# OSSIICB.net
KiCad netlist of a schematic drawn in EAGLE
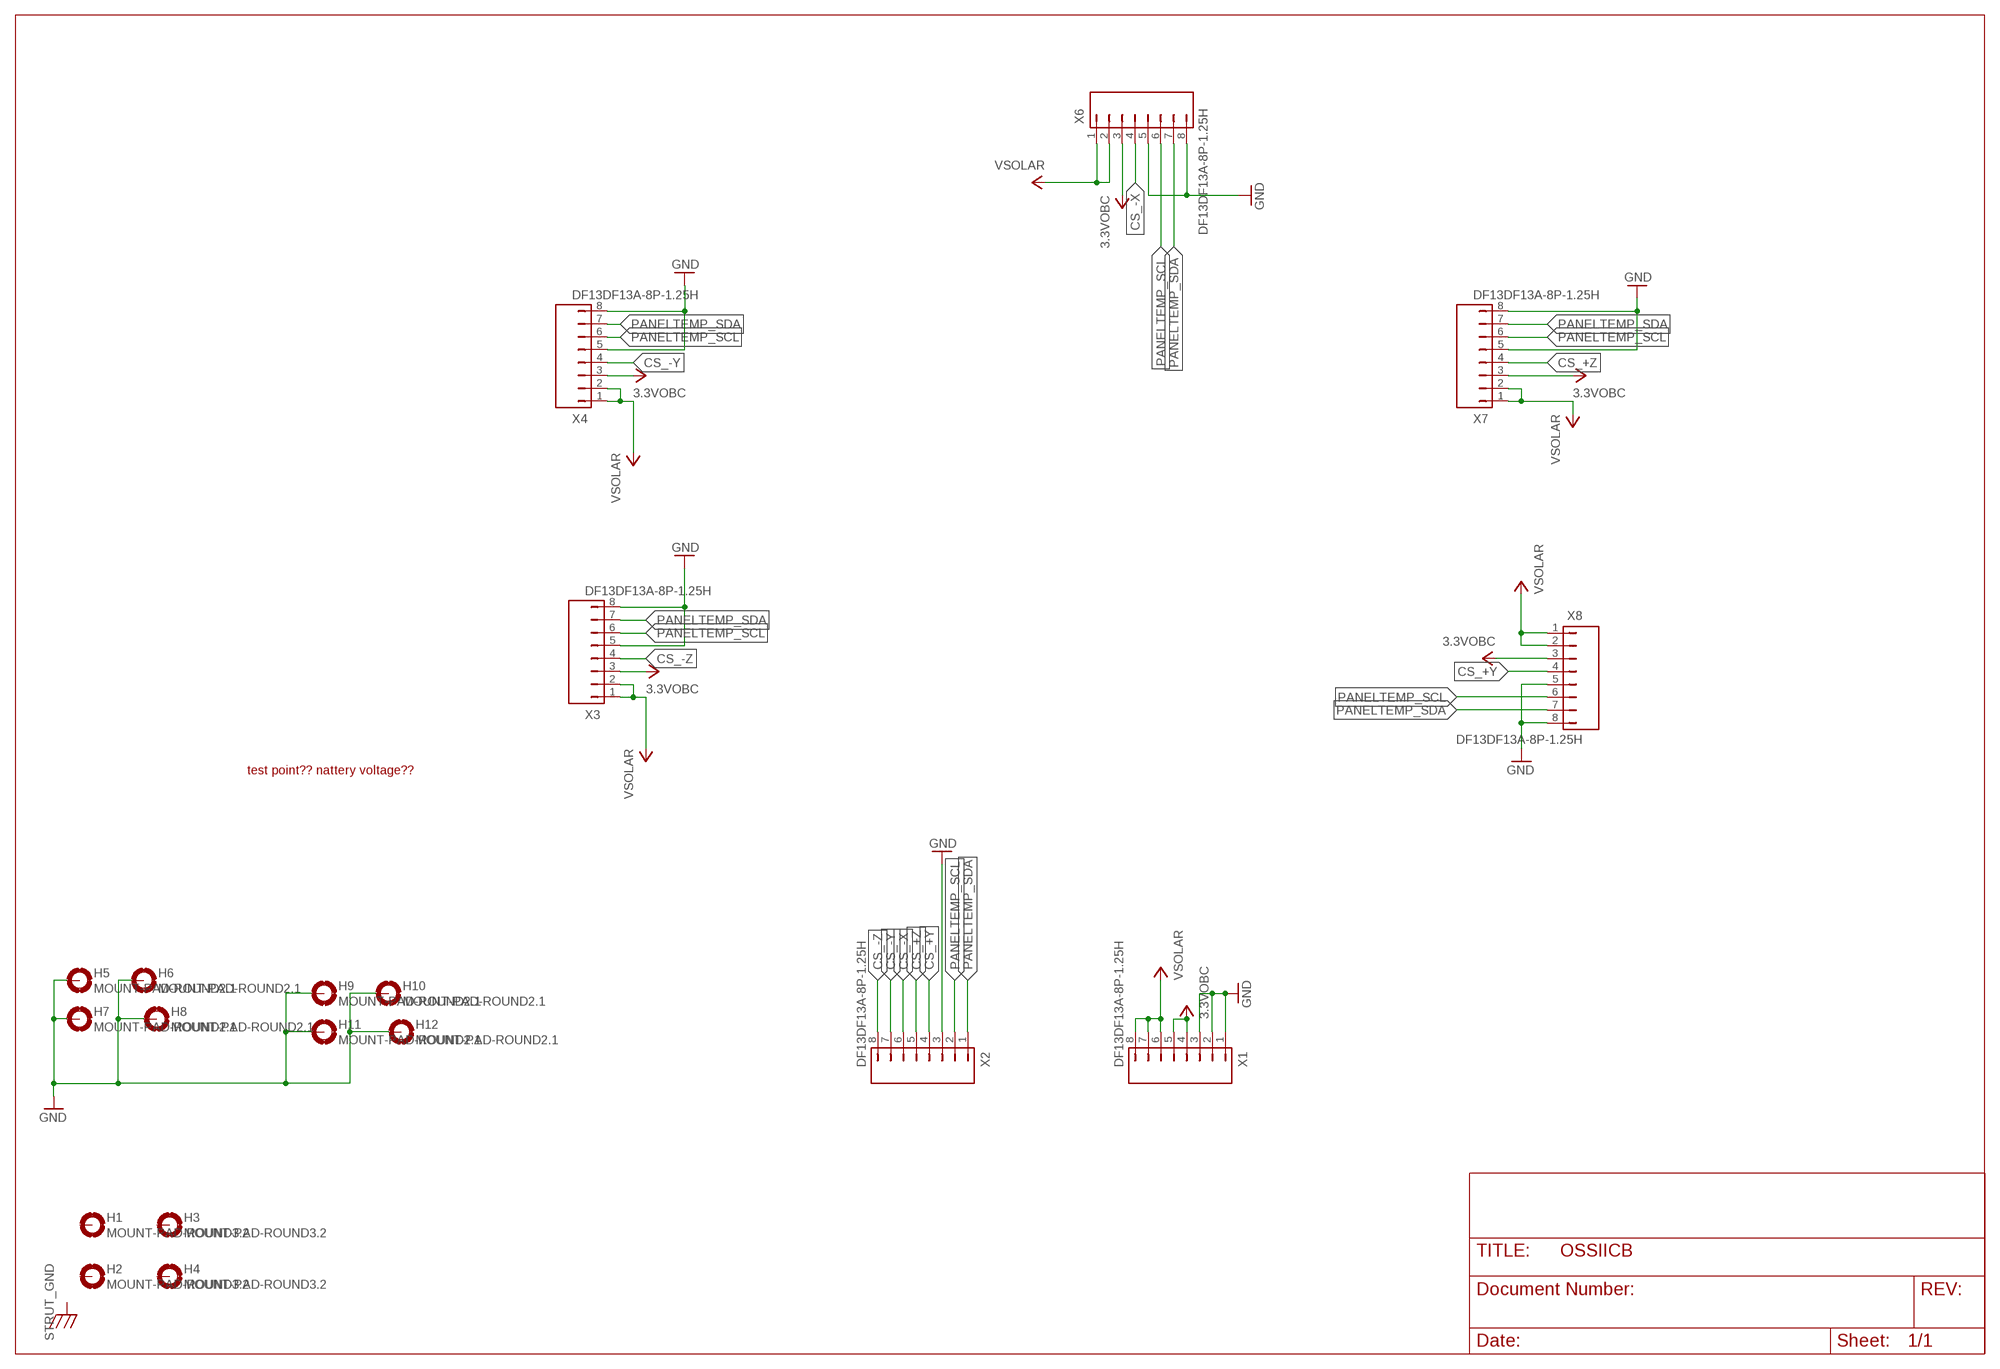
[diagram p0: schematic, sheet 1]

(export (version "E")
  (design (tool "Eeschema 10.0.6"))
  (components
    (comp (ref "H1")
      (value "MOUNT-PAD-ROUND3.2")
      (footprint "eagle-import:3.2-PAD-ROUND")
      (libsource (lib "eagle-import") (part "MOUNT-PAD-ROUND3.2"))
    )
    (comp (ref "H2")
      (value "MOUNT-PAD-ROUND3.2")
      (footprint "eagle-import:3.2-PAD-ROUND")
      (libsource (lib "eagle-import") (part "MOUNT-PAD-ROUND3.2"))
    )
    (comp (ref "H3")
      (value "MOUNT-PAD-ROUND3.2")
      (footprint "eagle-import:3.2-PAD-ROUND")
      (libsource (lib "eagle-import") (part "MOUNT-PAD-ROUND3.2"))
    )
    (comp (ref "H4")
      (value "MOUNT-PAD-ROUND3.2")
      (footprint "eagle-import:3.2-PAD-ROUND")
      (libsource (lib "eagle-import") (part "MOUNT-PAD-ROUND3.2"))
    )
    (comp (ref "H5")
      (value "MOUNT-PAD-ROUND2.1")
      (footprint "eagle-import:2.1-PAD-ROUND")
      (libsource (lib "eagle-import") (part "MOUNT-PAD-ROUND2.1"))
    )
    (comp (ref "H6")
      (value "MOUNT-PAD-ROUND2.1")
      (footprint "eagle-import:2.1-PAD-ROUND")
      (libsource (lib "eagle-import") (part "MOUNT-PAD-ROUND2.1"))
    )
    (comp (ref "H7")
      (value "MOUNT-PAD-ROUND2.1")
      (footprint "eagle-import:2.1-PAD-ROUND")
      (libsource (lib "eagle-import") (part "MOUNT-PAD-ROUND2.1"))
    )
    (comp (ref "H8")
      (value "MOUNT-PAD-ROUND2.1")
      (footprint "eagle-import:2.1-PAD-ROUND")
      (libsource (lib "eagle-import") (part "MOUNT-PAD-ROUND2.1"))
    )
    (comp (ref "H9")
      (value "MOUNT-PAD-ROUND2.1")
      (footprint "eagle-import:2.1-PAD-ROUND")
      (libsource (lib "eagle-import") (part "MOUNT-PAD-ROUND2.1"))
    )
    (comp (ref "H10")
      (value "MOUNT-PAD-ROUND2.1")
      (footprint "eagle-import:2.1-PAD-ROUND")
      (libsource (lib "eagle-import") (part "MOUNT-PAD-ROUND2.1"))
    )
    (comp (ref "H11")
      (value "MOUNT-PAD-ROUND2.1")
      (footprint "eagle-import:2.1-PAD-ROUND")
      (libsource (lib "eagle-import") (part "MOUNT-PAD-ROUND2.1"))
    )
    (comp (ref "H12")
      (value "MOUNT-PAD-ROUND2.1")
      (footprint "eagle-import:2.1-PAD-ROUND")
      (libsource (lib "eagle-import") (part "MOUNT-PAD-ROUND2.1"))
    )
    (comp (ref "X1")
      (value "DF13DF13A-8P-1.25H")
      (footprint "eagle-import:DF13A-8P")
      (libsource (lib "eagle-import") (part "DF13DF13A-8P-1.25H"))
    )
    (comp (ref "X2")
      (value "DF13DF13A-8P-1.25H")
      (footprint "eagle-import:DF13A-8P")
      (libsource (lib "eagle-import") (part "DF13DF13A-8P-1.25H"))
    )
    (comp (ref "X3")
      (value "DF13DF13A-8P-1.25H")
      (footprint "eagle-import:DF13A-8P")
      (libsource (lib "eagle-import") (part "DF13DF13A-8P-1.25H"))
    )
    (comp (ref "X4")
      (value "DF13DF13A-8P-1.25H")
      (footprint "eagle-import:DF13A-8P")
      (libsource (lib "eagle-import") (part "DF13DF13A-8P-1.25H"))
    )
    (comp (ref "X6")
      (value "DF13DF13A-8P-1.25H")
      (footprint "eagle-import:DF13A-8P")
      (libsource (lib "eagle-import") (part "DF13DF13A-8P-1.25H"))
    )
    (comp (ref "X7")
      (value "DF13DF13A-8P-1.25H")
      (footprint "eagle-import:DF13A-8P")
      (libsource (lib "eagle-import") (part "DF13DF13A-8P-1.25H"))
    )
    (comp (ref "X8")
      (value "DF13DF13A-8P-1.25H")
      (footprint "eagle-import:DF13A-8P")
      (libsource (lib "eagle-import") (part "DF13DF13A-8P-1.25H"))
    )
  )
  (nets
    (net (code "1") (name "3.3VOBC") (class "Default")
      (node (ref "X1") (pin "4") (pinfunction "4_4") (pintype "passive"))
      (node (ref "X1") (pin "5") (pinfunction "5_5") (pintype "passive"))
      (node (ref "X3") (pin "3") (pinfunction "3_3") (pintype "passive"))
      (node (ref "X4") (pin "3") (pinfunction "3_3") (pintype "passive"))
      (node (ref "X6") (pin "3") (pinfunction "3_3") (pintype "passive"))
      (node (ref "X7") (pin "3") (pinfunction "3_3") (pintype "passive"))
      (node (ref "X8") (pin "3") (pinfunction "3_3") (pintype "passive"))
    )
    (net (code "2") (name "CS_+Y") (class "Default")
      (node (ref "X2") (pin "4") (pinfunction "4_4") (pintype "passive"))
      (node (ref "X8") (pin "4") (pinfunction "4_4") (pintype "passive"))
    )
    (net (code "3") (name "CS_+Z") (class "Default")
      (node (ref "X2") (pin "5") (pinfunction "5_5") (pintype "passive"))
      (node (ref "X7") (pin "4") (pinfunction "4_4") (pintype "passive"))
    )
    (net (code "4") (name "CS_-X") (class "Default")
      (node (ref "X2") (pin "6") (pinfunction "6_6") (pintype "passive"))
      (node (ref "X6") (pin "4") (pinfunction "4_4") (pintype "passive"))
    )
    (net (code "5") (name "CS_-Y") (class "Default")
      (node (ref "X2") (pin "7") (pinfunction "7_7") (pintype "passive"))
      (node (ref "X4") (pin "4") (pinfunction "4_4") (pintype "passive"))
    )
    (net (code "6") (name "CS_-Z") (class "Default")
      (node (ref "X2") (pin "8") (pinfunction "8_8") (pintype "passive"))
      (node (ref "X3") (pin "4") (pinfunction "4_4") (pintype "passive"))
    )
    (net (code "7") (name "GND") (class "Default")
      (node (ref "H10") (pin "B3,2") (pinfunction "MOUNT_B3,2") (pintype "passive"))
      (node (ref "H11") (pin "B3,2") (pinfunction "MOUNT_B3,2") (pintype "passive"))
      (node (ref "H12") (pin "B3,2") (pinfunction "MOUNT_B3,2") (pintype "passive"))
      (node (ref "H5") (pin "B3,2") (pinfunction "MOUNT_B3,2") (pintype "passive"))
      (node (ref "H6") (pin "B3,2") (pinfunction "MOUNT_B3,2") (pintype "passive"))
      (node (ref "H7") (pin "B3,2") (pinfunction "MOUNT_B3,2") (pintype "passive"))
      (node (ref "H8") (pin "B3,2") (pinfunction "MOUNT_B3,2") (pintype "passive"))
      (node (ref "H9") (pin "B3,2") (pinfunction "MOUNT_B3,2") (pintype "passive"))
      (node (ref "X1") (pin "1") (pinfunction "1_1") (pintype "passive"))
      (node (ref "X1") (pin "2") (pinfunction "2_2") (pintype "passive"))
      (node (ref "X1") (pin "3") (pinfunction "3_3") (pintype "passive"))
      (node (ref "X2") (pin "3") (pinfunction "3_3") (pintype "passive"))
      (node (ref "X3") (pin "5") (pinfunction "5_5") (pintype "passive"))
      (node (ref "X3") (pin "8") (pinfunction "8_8") (pintype "passive"))
      (node (ref "X4") (pin "5") (pinfunction "5_5") (pintype "passive"))
      (node (ref "X4") (pin "8") (pinfunction "8_8") (pintype "passive"))
      (node (ref "X6") (pin "5") (pinfunction "5_5") (pintype "passive"))
      (node (ref "X6") (pin "8") (pinfunction "8_8") (pintype "passive"))
      (node (ref "X7") (pin "5") (pinfunction "5_5") (pintype "passive"))
      (node (ref "X7") (pin "8") (pinfunction "8_8") (pintype "passive"))
      (node (ref "X8") (pin "5") (pinfunction "5_5") (pintype "passive"))
      (node (ref "X8") (pin "8") (pinfunction "8_8") (pintype "passive"))
    )
    (net (code "8") (name "PANELTEMP_SCL") (class "Default")
      (node (ref "X2") (pin "2") (pinfunction "2_2") (pintype "passive"))
      (node (ref "X3") (pin "6") (pinfunction "6_6") (pintype "passive"))
      (node (ref "X4") (pin "6") (pinfunction "6_6") (pintype "passive"))
      (node (ref "X6") (pin "6") (pinfunction "6_6") (pintype "passive"))
      (node (ref "X7") (pin "6") (pinfunction "6_6") (pintype "passive"))
      (node (ref "X8") (pin "6") (pinfunction "6_6") (pintype "passive"))
    )
    (net (code "9") (name "PANELTEMP_SDA") (class "Default")
      (node (ref "X2") (pin "1") (pinfunction "1_1") (pintype "passive"))
      (node (ref "X3") (pin "7") (pinfunction "7_7") (pintype "passive"))
      (node (ref "X4") (pin "7") (pinfunction "7_7") (pintype "passive"))
      (node (ref "X6") (pin "7") (pinfunction "7_7") (pintype "passive"))
      (node (ref "X7") (pin "7") (pinfunction "7_7") (pintype "passive"))
      (node (ref "X8") (pin "7") (pinfunction "7_7") (pintype "passive"))
    )
    (net (code "11") (name "VSOLAR") (class "Default")
      (node (ref "X1") (pin "6") (pinfunction "6_6") (pintype "passive"))
      (node (ref "X1") (pin "7") (pinfunction "7_7") (pintype "passive"))
      (node (ref "X1") (pin "8") (pinfunction "8_8") (pintype "passive"))
      (node (ref "X3") (pin "1") (pinfunction "1_1") (pintype "passive"))
      (node (ref "X3") (pin "2") (pinfunction "2_2") (pintype "passive"))
      (node (ref "X4") (pin "1") (pinfunction "1_1") (pintype "passive"))
      (node (ref "X4") (pin "2") (pinfunction "2_2") (pintype "passive"))
      (node (ref "X6") (pin "1") (pinfunction "1_1") (pintype "passive"))
      (node (ref "X6") (pin "2") (pinfunction "2_2") (pintype "passive"))
      (node (ref "X7") (pin "1") (pinfunction "1_1") (pintype "passive"))
      (node (ref "X7") (pin "2") (pinfunction "2_2") (pintype "passive"))
      (node (ref "X8") (pin "1") (pinfunction "1_1") (pintype "passive"))
      (node (ref "X8") (pin "2") (pinfunction "2_2") (pintype "passive"))
    )
    (net (code "12") (name "unconnected-(H1-MOUNT-PadB3,2)") (class "Default")
      (node (ref "H1") (pin "B3,2") (pinfunction "MOUNT_B3,2") (pintype "passive"))
    )
    (net (code "13") (name "unconnected-(H2-MOUNT-PadB3,2)") (class "Default")
      (node (ref "H2") (pin "B3,2") (pinfunction "MOUNT_B3,2") (pintype "passive"))
    )
    (net (code "14") (name "unconnected-(H3-MOUNT-PadB3,2)") (class "Default")
      (node (ref "H3") (pin "B3,2") (pinfunction "MOUNT_B3,2") (pintype "passive"))
    )
    (net (code "15") (name "unconnected-(H4-MOUNT-PadB3,2)") (class "Default")
      (node (ref "H4") (pin "B3,2") (pinfunction "MOUNT_B3,2") (pintype "passive"))
    )
  )
)
